# cheetah_driver_3.net
KiCad netlist of a schematic drawn in EAGLE
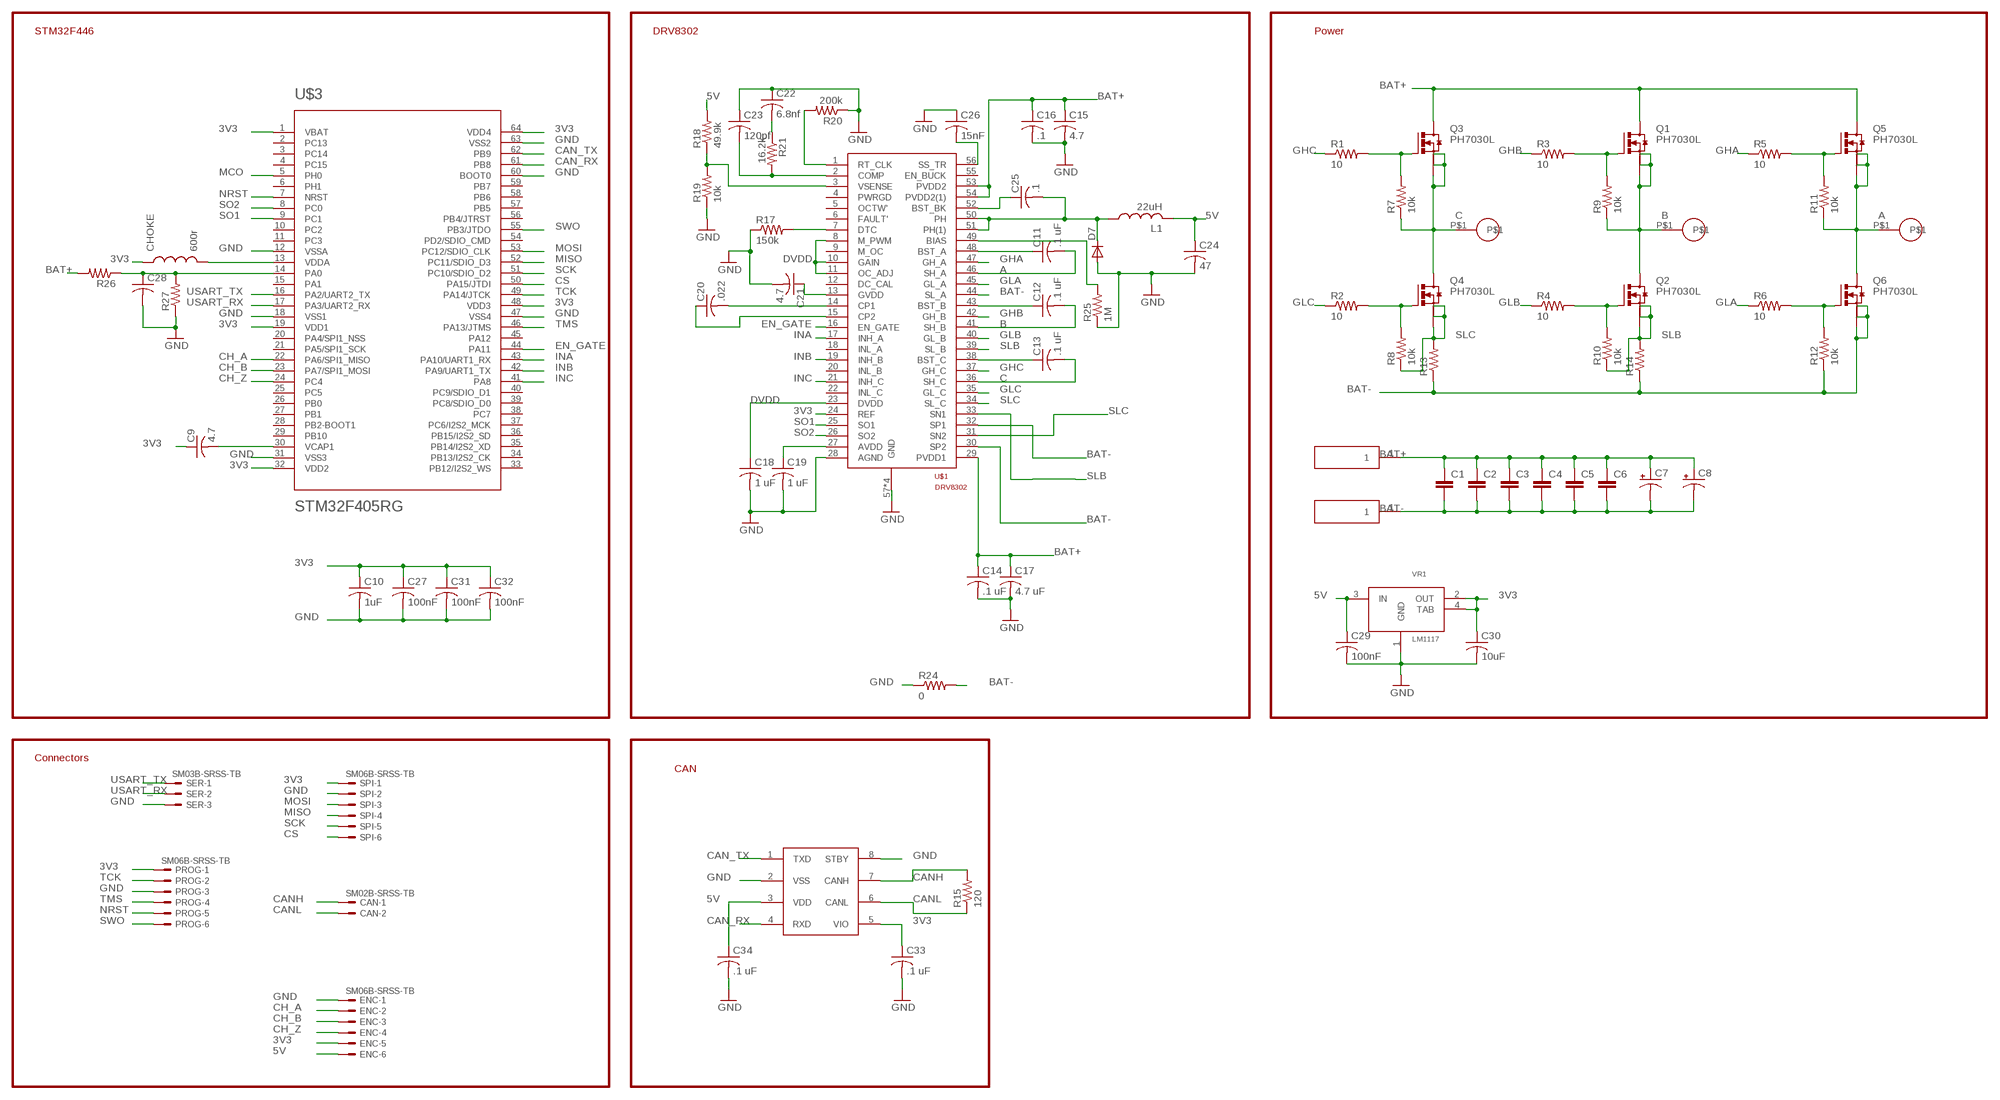
[diagram p0: schematic, sheet 1]

(export (version "E")
  (design (tool "Eeschema 10.0.6"))
  (components
    (comp (ref "C1")
      (value "C-EUC0805")
      (footprint "eagle-import:C0805")
      (libsource (lib "eagle-import") (part "C-EUC0805"))
    )
    (comp (ref "C2")
      (value "C-EUC0805")
      (footprint "eagle-import:C0805")
      (libsource (lib "eagle-import") (part "C-EUC0805"))
    )
    (comp (ref "C3")
      (value "C-EUC0805")
      (footprint "eagle-import:C0805")
      (libsource (lib "eagle-import") (part "C-EUC0805"))
    )
    (comp (ref "C4")
      (value "C-EUC0805")
      (footprint "eagle-import:C0805")
      (libsource (lib "eagle-import") (part "C-EUC0805"))
    )
    (comp (ref "C5")
      (value "C-EUC0805")
      (footprint "eagle-import:C0805")
      (libsource (lib "eagle-import") (part "C-EUC0805"))
    )
    (comp (ref "C6")
      (value "C-EUC0805")
      (footprint "eagle-import:C0805")
      (libsource (lib "eagle-import") (part "C-EUC0805"))
    )
    (comp (ref "C7")
      (value "CPOL-USE3.5-8")
      (footprint "eagle-import:E3,5-8")
      (libsource (lib "eagle-import") (part "CPOL-USE3.5-8"))
    )
    (comp (ref "C8")
      (value "CPOL-USE3.5-8")
      (footprint "eagle-import:E3,5-8")
      (libsource (lib "eagle-import") (part "CPOL-USE3.5-8"))
    )
    (comp (ref "C9")
      (value "4.7")
      (footprint "eagle-import:C0603")
      (libsource (lib "eagle-import") (part "C-USC0603"))
    )
    (comp (ref "C10")
      (value "1uF")
      (footprint "eagle-import:C0603")
      (libsource (lib "eagle-import") (part "C-USC0603"))
    )
    (comp (ref "C11")
      (value ".1 uF")
      (footprint "eagle-import:C0603")
      (libsource (lib "eagle-import") (part "C-USC0603"))
    )
    (comp (ref "C12")
      (value ".1 uF")
      (footprint "eagle-import:C0603")
      (libsource (lib "eagle-import") (part "C-USC0603"))
    )
    (comp (ref "C13")
      (value ".1 uF")
      (footprint "eagle-import:C0603")
      (libsource (lib "eagle-import") (part "C-USC0603"))
    )
    (comp (ref "C14")
      (value ".1 uF")
      (footprint "eagle-import:C0603")
      (libsource (lib "eagle-import") (part "C-USC0603"))
    )
    (comp (ref "C15")
      (value "4.7")
      (footprint "eagle-import:C0805")
      (libsource (lib "eagle-import") (part "C-USC0805"))
    )
    (comp (ref "C16")
      (value ".1")
      (footprint "eagle-import:C0603")
      (libsource (lib "eagle-import") (part "C-USC0603"))
    )
    (comp (ref "C17")
      (value "4.7 uF")
      (footprint "eagle-import:C0805")
      (libsource (lib "eagle-import") (part "C-USC0805"))
    )
    (comp (ref "C18")
      (value "1 uF")
      (footprint "eagle-import:C0603")
      (libsource (lib "eagle-import") (part "C-USC0603"))
    )
    (comp (ref "C19")
      (value "1 uF")
      (footprint "eagle-import:C0603")
      (libsource (lib "eagle-import") (part "C-USC0603"))
    )
    (comp (ref "C20")
      (value ".022")
      (footprint "eagle-import:C0603")
      (libsource (lib "eagle-import") (part "C-USC0603"))
    )
    (comp (ref "C21")
      (value "4.7")
      (footprint "eagle-import:C0805")
      (libsource (lib "eagle-import") (part "C-USC0805"))
    )
    (comp (ref "C22")
      (value "6.8nf")
      (footprint "eagle-import:C0603")
      (libsource (lib "eagle-import") (part "C-USC0603"))
    )
    (comp (ref "C23")
      (value "120pf")
      (footprint "eagle-import:C0603")
      (libsource (lib "eagle-import") (part "C-USC0603"))
    )
    (comp (ref "C24")
      (value "47")
      (footprint "eagle-import:C1210")
      (libsource (lib "eagle-import") (part "C-USC1210"))
    )
    (comp (ref "C25")
      (value ".1")
      (footprint "eagle-import:C0603")
      (libsource (lib "eagle-import") (part "C-USC0603"))
    )
    (comp (ref "C26")
      (value "15nF")
      (footprint "eagle-import:C0603")
      (libsource (lib "eagle-import") (part "C-USC0603"))
    )
    (comp (ref "C27")
      (value "100nF")
      (footprint "eagle-import:C0603")
      (libsource (lib "eagle-import") (part "C-USC0603"))
    )
    (comp (ref "C28")
      (value "C-USC0603")
      (footprint "eagle-import:C0603")
      (libsource (lib "eagle-import") (part "C-USC0603"))
    )
    (comp (ref "C29")
      (value "100nF")
      (footprint "eagle-import:C0603")
      (libsource (lib "eagle-import") (part "C-USC0603"))
    )
    (comp (ref "C30")
      (value "10uF")
      (footprint "eagle-import:C0603")
      (libsource (lib "eagle-import") (part "C-USC0603"))
    )
    (comp (ref "C31")
      (value "100nF")
      (footprint "eagle-import:C0603")
      (libsource (lib "eagle-import") (part "C-USC0603"))
    )
    (comp (ref "C32")
      (value "100nF")
      (footprint "eagle-import:C0603")
      (libsource (lib "eagle-import") (part "C-USC0603"))
    )
    (comp (ref "C33")
      (value ".1 uF")
      (footprint "eagle-import:C0603K")
      (libsource (lib "eagle-import") (part "C-USC0603K"))
    )
    (comp (ref "C34")
      (value ".1 uF")
      (footprint "eagle-import:C0603K")
      (libsource (lib "eagle-import") (part "C-USC0603K"))
    )
    (comp (ref "CAN")
      (value "SM02B-SRSS-TB")
      (footprint "eagle-import:SM02B-SRSS-TB")
      (libsource (lib "eagle-import") (part "?M02B-SRSS-TBS"))
    )
    (comp (ref "CHOKE")
      (value "600r")
      (footprint "eagle-import:0603")
      (libsource (lib "eagle-import") (part "INDUCTOR0603"))
    )
    (comp (ref "D7")
      (value "DIODE-DO-214AC")
      (footprint "eagle-import:DO-214AC")
      (libsource (lib "eagle-import") (part "DIODE-DO-214AC"))
    )
    (comp (ref "ENC")
      (value "SM06B-SRSS-TB")
      (footprint "eagle-import:SM06B-SRSS-TB")
      (libsource (lib "eagle-import") (part "?M06B-SRSS-TBS"))
    )
    (comp (ref "J4")
      (value "0.125_PAD")
      (footprint "eagle-import:0.125_PAD")
      (libsource (lib "eagle-import") (part "0.125_PAD"))
    )
    (comp (ref "J5")
      (value "0.125_PAD")
      (footprint "eagle-import:0.125_PAD")
      (libsource (lib "eagle-import") (part "0.125_PAD"))
    )
    (comp (ref "L1")
      (value "22uH")
      (footprint "eagle-import:L4532P")
      (libsource (lib "eagle-import") (part "L-USL4532P"))
    )
    (comp (ref "PROG")
      (value "SM06B-SRSS-TB")
      (footprint "eagle-import:SM06B-SRSS-TB")
      (libsource (lib "eagle-import") (part "?M06B-SRSS-TBS"))
    )
    (comp (ref "Q1")
      (value "PH7030L")
      (footprint "eagle-import:SOT669")
      (libsource (lib "eagle-import") (part "PH7030L"))
    )
    (comp (ref "Q2")
      (value "PH7030L")
      (footprint "eagle-import:SOT669")
      (libsource (lib "eagle-import") (part "PH7030L"))
    )
    (comp (ref "Q3")
      (value "PH7030L")
      (footprint "eagle-import:SOT669")
      (libsource (lib "eagle-import") (part "PH7030L"))
    )
    (comp (ref "Q4")
      (value "PH7030L")
      (footprint "eagle-import:SOT669")
      (libsource (lib "eagle-import") (part "PH7030L"))
    )
    (comp (ref "Q5")
      (value "PH7030L")
      (footprint "eagle-import:SOT669")
      (libsource (lib "eagle-import") (part "PH7030L"))
    )
    (comp (ref "Q6")
      (value "PH7030L")
      (footprint "eagle-import:SOT669")
      (libsource (lib "eagle-import") (part "PH7030L"))
    )
    (comp (ref "R1")
      (value "10")
      (footprint "eagle-import:R0603")
      (libsource (lib "eagle-import") (part "R-US_R0603"))
    )
    (comp (ref "R2")
      (value "10")
      (footprint "eagle-import:R0603")
      (libsource (lib "eagle-import") (part "R-US_R0603"))
    )
    (comp (ref "R3")
      (value "10")
      (footprint "eagle-import:R0603")
      (libsource (lib "eagle-import") (part "R-US_R0603"))
    )
    (comp (ref "R4")
      (value "10")
      (footprint "eagle-import:R0603")
      (libsource (lib "eagle-import") (part "R-US_R0603"))
    )
    (comp (ref "R5")
      (value "10")
      (footprint "eagle-import:R0603")
      (libsource (lib "eagle-import") (part "R-US_R0603"))
    )
    (comp (ref "R6")
      (value "10")
      (footprint "eagle-import:R0603")
      (libsource (lib "eagle-import") (part "R-US_R0603"))
    )
    (comp (ref "R7")
      (value "10k")
      (footprint "eagle-import:R0603")
      (libsource (lib "eagle-import") (part "R-US_R0603"))
    )
    (comp (ref "R8")
      (value "10k")
      (footprint "eagle-import:R0603")
      (libsource (lib "eagle-import") (part "R-US_R0603"))
    )
    (comp (ref "R9")
      (value "10k")
      (footprint "eagle-import:R0603")
      (libsource (lib "eagle-import") (part "R-US_R0603"))
    )
    (comp (ref "R10")
      (value "10k")
      (footprint "eagle-import:R0603")
      (libsource (lib "eagle-import") (part "R-US_R0603"))
    )
    (comp (ref "R11")
      (value "10k")
      (footprint "eagle-import:R0603")
      (libsource (lib "eagle-import") (part "R-US_R0603"))
    )
    (comp (ref "R12")
      (value "10k")
      (footprint "eagle-import:R0603")
      (libsource (lib "eagle-import") (part "R-US_R0603"))
    )
    (comp (ref "R13")
      (value "R-US_R1210")
      (footprint "eagle-import:R1210")
      (libsource (lib "eagle-import") (part "R-US_R1210"))
    )
    (comp (ref "R14")
      (value "R-US_R1210")
      (footprint "eagle-import:R1210")
      (libsource (lib "eagle-import") (part "R-US_R1210"))
    )
    (comp (ref "R15")
      (value "120")
      (footprint "eagle-import:R0603")
      (libsource (lib "eagle-import") (part "R-US_R0603"))
    )
    (comp (ref "R17")
      (value "150k")
      (footprint "eagle-import:R0603")
      (libsource (lib "eagle-import") (part "R-US_R0603"))
    )
    (comp (ref "R18")
      (value "49.9k")
      (footprint "eagle-import:R0603")
      (libsource (lib "eagle-import") (part "R-US_R0603"))
    )
    (comp (ref "R19")
      (value "10k")
      (footprint "eagle-import:R0603")
      (libsource (lib "eagle-import") (part "R-US_R0603"))
    )
    (comp (ref "R20")
      (value "200k")
      (footprint "eagle-import:R0603")
      (libsource (lib "eagle-import") (part "R-US_R0603"))
    )
    (comp (ref "R21")
      (value "16.2k")
      (footprint "eagle-import:R0603")
      (libsource (lib "eagle-import") (part "R-US_R0603"))
    )
    (comp (ref "R24")
      (value "0")
      (footprint "eagle-import:R0603")
      (libsource (lib "eagle-import") (part "R-US_R0603"))
    )
    (comp (ref "R25")
      (value "1M")
      (footprint "eagle-import:R0603")
      (libsource (lib "eagle-import") (part "R-US_R0603"))
    )
    (comp (ref "R26")
      (value "R-US_R0603")
      (footprint "eagle-import:R0603")
      (libsource (lib "eagle-import") (part "R-US_R0603"))
    )
    (comp (ref "R27")
      (value "R-US_R0603")
      (footprint "eagle-import:R0603")
      (libsource (lib "eagle-import") (part "R-US_R0603"))
    )
    (comp (ref "SER")
      (value "SM03B-SRSS-TB")
      (footprint "eagle-import:SM03B-SRSS-TB")
      (libsource (lib "eagle-import") (part "?M03B-SRSS-TBS"))
    )
    (comp (ref "SPI")
      (value "SM06B-SRSS-TB")
      (footprint "eagle-import:SM06B-SRSS-TB")
      (libsource (lib "eagle-import") (part "?M06B-SRSS-TBS"))
    )
    (comp (ref "U$1")
      (value "DRV8302")
      (footprint "eagle-import:HTSSOP56")
      (libsource (lib "eagle-import") (part "DRV8302"))
    )
    (comp (ref "U$2")
      (value "18_AWG_PAD")
      (footprint "eagle-import:18_AWG_PAD")
      (libsource (lib "eagle-import") (part "18_AWG_PAD"))
    )
    (comp (ref "U$3")
      (value "STM32F405RG")
      (footprint "eagle-import:TQFP64")
      (libsource (lib "eagle-import") (part "STM32F405RG"))
    )
    (comp (ref "U$4")
      (value "18_AWG_PAD")
      (footprint "eagle-import:18_AWG_PAD")
      (libsource (lib "eagle-import") (part "18_AWG_PAD"))
    )
    (comp (ref "U$5")
      (value "18_AWG_PAD")
      (footprint "eagle-import:18_AWG_PAD")
      (libsource (lib "eagle-import") (part "18_AWG_PAD"))
    )
    (comp (ref "U$6")
      (value "MCP2561")
      (footprint "eagle-import:SO08")
      (libsource (lib "eagle-import") (part "MCP2561"))
    )
    (comp (ref "VR1")
      (value "LM1117")
      (footprint "eagle-import:SOT-223")
      (libsource (lib "eagle-import") (part "LM1117"))
    )
  )
  (nets
    (net (code "1") (name "/3V3") (class "Default")
      (node (ref "C10") (pin "1") (pinfunction "1_1") (pintype "passive"))
      (node (ref "C27") (pin "1") (pinfunction "1_1") (pintype "passive"))
      (node (ref "C30") (pin "1") (pinfunction "1_1") (pintype "passive"))
      (node (ref "C31") (pin "1") (pinfunction "1_1") (pintype "passive"))
      (node (ref "C32") (pin "1") (pinfunction "1_1") (pintype "passive"))
      (node (ref "C33") (pin "1") (pinfunction "1_1") (pintype "passive"))
      (node (ref "C9") (pin "1") (pinfunction "1_1") (pintype "passive"))
      (node (ref "CHOKE") (pin "1") (pinfunction "1_1") (pintype "passive"))
      (node (ref "ENC") (pin "5") (pinfunction "S_5") (pintype "passive"))
      (node (ref "PROG") (pin "1") (pinfunction "S_1") (pintype "passive"))
      (node (ref "SPI") (pin "1") (pinfunction "S_1") (pintype "passive"))
      (node (ref "U$1") (pin "24") (pinfunction "REF_24") (pintype "bidirectional"))
      (node (ref "U$3") (pin "1") (pinfunction "VBAT_1") (pintype "bidirectional"))
      (node (ref "U$3") (pin "19") (pinfunction "VDD1_19") (pintype "bidirectional"))
      (node (ref "U$3") (pin "32") (pinfunction "VDD2_32") (pintype "bidirectional"))
      (node (ref "U$3") (pin "48") (pinfunction "VDD3_48") (pintype "bidirectional"))
      (node (ref "U$3") (pin "64") (pinfunction "VDD4_64") (pintype "bidirectional"))
      (node (ref "U$6") (pin "5") (pinfunction "VIO_5") (pintype "bidirectional"))
      (node (ref "VR1") (pin "2") (pinfunction "OUT_2") (pintype "bidirectional"))
      (node (ref "VR1") (pin "4") (pinfunction "TAB_4") (pintype "bidirectional"))
    )
    (net (code "2") (name "/5V") (class "Default")
      (node (ref "C24") (pin "1") (pinfunction "1_1") (pintype "passive"))
      (node (ref "C29") (pin "1") (pinfunction "1_1") (pintype "passive"))
      (node (ref "C34") (pin "1") (pinfunction "1_1") (pintype "passive"))
      (node (ref "ENC") (pin "6") (pinfunction "S_6") (pintype "passive"))
      (node (ref "L1") (pin "2") (pinfunction "2_2") (pintype "passive"))
      (node (ref "R18") (pin "2") (pinfunction "2_2") (pintype "passive"))
      (node (ref "U$6") (pin "3") (pinfunction "VDD_3") (pintype "bidirectional"))
      (node (ref "VR1") (pin "3") (pinfunction "IN_3") (pintype "bidirectional"))
    )
    (net (code "3") (name "/A") (class "Default")
      (node (ref "C11") (pin "2") (pinfunction "2_2") (pintype "passive"))
      (node (ref "Q5") (pin "1") (pinfunction "S_1") (pintype "passive"))
      (node (ref "Q5") (pin "2") (pinfunction "S_2") (pintype "passive"))
      (node (ref "Q5") (pin "3") (pinfunction "S_3") (pintype "passive"))
      (node (ref "Q6") (pin "MB") (pinfunction "D_MB") (pintype "passive"))
      (node (ref "R11") (pin "1") (pinfunction "1_1") (pintype "passive"))
      (node (ref "U$1") (pin "46") (pinfunction "SH_A_46") (pintype "bidirectional"))
      (node (ref "U$5") (pin "P$1") (pinfunction "P$1_P$1") (pintype "bidirectional"))
    )
    (net (code "4") (name "/B") (class "Default")
      (node (ref "C12") (pin "2") (pinfunction "2_2") (pintype "passive"))
      (node (ref "Q1") (pin "1") (pinfunction "S_1") (pintype "passive"))
      (node (ref "Q1") (pin "2") (pinfunction "S_2") (pintype "passive"))
      (node (ref "Q1") (pin "3") (pinfunction "S_3") (pintype "passive"))
      (node (ref "Q2") (pin "MB") (pinfunction "D_MB") (pintype "passive"))
      (node (ref "R9") (pin "1") (pinfunction "1_1") (pintype "passive"))
      (node (ref "U$1") (pin "41") (pinfunction "SH_B_41") (pintype "bidirectional"))
      (node (ref "U$4") (pin "P$1") (pinfunction "P$1_P$1") (pintype "bidirectional"))
    )
    (net (code "5") (name "/BAT+") (class "Default")
      (node (ref "C1") (pin "1") (pinfunction "1_1") (pintype "passive"))
      (node (ref "C14") (pin "1") (pinfunction "1_1") (pintype "passive"))
      (node (ref "C15") (pin "1") (pinfunction "1_1") (pintype "passive"))
      (node (ref "C16") (pin "1") (pinfunction "1_1") (pintype "passive"))
      (node (ref "C17") (pin "1") (pinfunction "1_1") (pintype "passive"))
      (node (ref "C2") (pin "1") (pinfunction "1_1") (pintype "passive"))
      (node (ref "C3") (pin "1") (pinfunction "1_1") (pintype "passive"))
      (node (ref "C4") (pin "1") (pinfunction "1_1") (pintype "passive"))
      (node (ref "C5") (pin "1") (pinfunction "1_1") (pintype "passive"))
      (node (ref "C6") (pin "1") (pinfunction "1_1") (pintype "passive"))
      (node (ref "C7") (pin "+") (pinfunction "+_+") (pintype "passive"))
      (node (ref "C8") (pin "+") (pinfunction "+_+") (pintype "passive"))
      (node (ref "J4") (pin "1") (pinfunction "1_1") (pintype "bidirectional"))
      (node (ref "Q1") (pin "MB") (pinfunction "D_MB") (pintype "passive"))
      (node (ref "Q3") (pin "MB") (pinfunction "D_MB") (pintype "passive"))
      (node (ref "Q5") (pin "MB") (pinfunction "D_MB") (pintype "passive"))
      (node (ref "R26") (pin "2") (pinfunction "2_2") (pintype "passive"))
      (node (ref "U$1") (pin "29") (pinfunction "PVDD1_29") (pintype "bidirectional"))
      (node (ref "U$1") (pin "53") (pinfunction "PVDD2_53") (pintype "bidirectional"))
      (node (ref "U$1") (pin "54") (pinfunction "PVDD2(1)_54") (pintype "bidirectional"))
    )
    (net (code "6") (name "/BAT-") (class "Default")
      (node (ref "C1") (pin "2") (pinfunction "2_2") (pintype "passive"))
      (node (ref "C2") (pin "2") (pinfunction "2_2") (pintype "passive"))
      (node (ref "C3") (pin "2") (pinfunction "2_2") (pintype "passive"))
      (node (ref "C4") (pin "2") (pinfunction "2_2") (pintype "passive"))
      (node (ref "C5") (pin "2") (pinfunction "2_2") (pintype "passive"))
      (node (ref "C6") (pin "2") (pinfunction "2_2") (pintype "passive"))
      (node (ref "C7") (pin "-") (pinfunction "-_-") (pintype "passive"))
      (node (ref "C8") (pin "-") (pinfunction "-_-") (pintype "passive"))
      (node (ref "J5") (pin "1") (pinfunction "1_1") (pintype "bidirectional"))
      (node (ref "Q6") (pin "1") (pinfunction "S_1") (pintype "passive"))
      (node (ref "Q6") (pin "2") (pinfunction "S_2") (pintype "passive"))
      (node (ref "Q6") (pin "3") (pinfunction "S_3") (pintype "passive"))
      (node (ref "R12") (pin "1") (pinfunction "1_1") (pintype "passive"))
      (node (ref "R13") (pin "1") (pinfunction "1_1") (pintype "passive"))
      (node (ref "R14") (pin "1") (pinfunction "1_1") (pintype "passive"))
      (node (ref "R24") (pin "2") (pinfunction "2_2") (pintype "passive"))
      (node (ref "U$1") (pin "30") (pinfunction "SP2_30") (pintype "bidirectional"))
      (node (ref "U$1") (pin "32") (pinfunction "SP1_32") (pintype "bidirectional"))
      (node (ref "U$1") (pin "44") (pinfunction "SL_A_44") (pintype "bidirectional"))
    )
    (net (code "7") (name "/C") (class "Default")
      (node (ref "C13") (pin "2") (pinfunction "2_2") (pintype "passive"))
      (node (ref "Q3") (pin "1") (pinfunction "S_1") (pintype "passive"))
      (node (ref "Q3") (pin "2") (pinfunction "S_2") (pintype "passive"))
      (node (ref "Q3") (pin "3") (pinfunction "S_3") (pintype "passive"))
      (node (ref "Q4") (pin "MB") (pinfunction "D_MB") (pintype "passive"))
      (node (ref "R7") (pin "1") (pinfunction "1_1") (pintype "passive"))
      (node (ref "U$1") (pin "36") (pinfunction "SH_C_36") (pintype "bidirectional"))
      (node (ref "U$2") (pin "P$1") (pinfunction "P$1_P$1") (pintype "bidirectional"))
    )
    (net (code "8") (name "/CANH") (class "Default")
      (node (ref "CAN") (pin "1") (pinfunction "S_1") (pintype "passive"))
      (node (ref "R15") (pin "2") (pinfunction "2_2") (pintype "passive"))
      (node (ref "U$6") (pin "7") (pinfunction "CANH_7") (pintype "bidirectional"))
    )
    (net (code "9") (name "/CANL") (class "Default")
      (node (ref "CAN") (pin "2") (pinfunction "S_2") (pintype "passive"))
      (node (ref "R15") (pin "1") (pinfunction "1_1") (pintype "passive"))
      (node (ref "U$6") (pin "6") (pinfunction "CANL_6") (pintype "bidirectional"))
    )
    (net (code "10") (name "/CAN_RX") (class "Default")
      (node (ref "U$3") (pin "61") (pinfunction "PB8_61") (pintype "bidirectional"))
      (node (ref "U$6") (pin "4") (pinfunction "RXD_4") (pintype "bidirectional"))
    )
    (net (code "11") (name "/CAN_TX") (class "Default")
      (node (ref "U$3") (pin "62") (pinfunction "PB9_62") (pintype "bidirectional"))
      (node (ref "U$6") (pin "1") (pinfunction "TXD_1") (pintype "bidirectional"))
    )
    (net (code "12") (name "/CH_A") (class "Default")
      (node (ref "ENC") (pin "2") (pinfunction "S_2") (pintype "passive"))
      (node (ref "U$3") (pin "22") (pinfunction "PA6/SPI1_MISO_22") (pintype "bidirectional"))
    )
    (net (code "13") (name "/CH_B") (class "Default")
      (node (ref "ENC") (pin "3") (pinfunction "S_3") (pintype "passive"))
      (node (ref "U$3") (pin "23") (pinfunction "PA7/SPI1_MOSI_23") (pintype "bidirectional"))
    )
    (net (code "14") (name "/CH_Z") (class "Default")
      (node (ref "ENC") (pin "4") (pinfunction "S_4") (pintype "passive"))
      (node (ref "U$3") (pin "24") (pinfunction "PC4_24") (pintype "bidirectional"))
    )
    (net (code "15") (name "/CS") (class "Default")
      (node (ref "SPI") (pin "6") (pinfunction "S_6") (pintype "passive"))
      (node (ref "U$3") (pin "50") (pinfunction "PA15/JTDI_50") (pintype "bidirectional"))
    )
    (net (code "16") (name "/DVDD") (class "Default")
      (node (ref "C18") (pin "1") (pinfunction "1_1") (pintype "passive"))
      (node (ref "U$1") (pin "10") (pinfunction "GAIN_10") (pintype "bidirectional"))
      (node (ref "U$1") (pin "11") (pinfunction "OC_ADJ_11") (pintype "bidirectional"))
      (node (ref "U$1") (pin "23") (pinfunction "DVDD_23") (pintype "bidirectional"))
      (node (ref "U$1") (pin "8") (pinfunction "M_PWM_8") (pintype "bidirectional"))
    )
    (net (code "17") (name "/EN_GATE") (class "Default")
      (node (ref "U$1") (pin "16") (pinfunction "EN_GATE_16") (pintype "bidirectional"))
      (node (ref "U$3") (pin "44") (pinfunction "PA11_44") (pintype "bidirectional"))
    )
    (net (code "18") (name "/GHA") (class "Default")
      (node (ref "R5") (pin "1") (pinfunction "1_1") (pintype "passive"))
      (node (ref "U$1") (pin "47") (pinfunction "GH_A_47") (pintype "bidirectional"))
    )
    (net (code "19") (name "/GHB") (class "Default")
      (node (ref "R3") (pin "1") (pinfunction "1_1") (pintype "passive"))
      (node (ref "U$1") (pin "42") (pinfunction "GH_B_42") (pintype "bidirectional"))
    )
    (net (code "20") (name "/GHC") (class "Default")
      (node (ref "R1") (pin "1") (pinfunction "1_1") (pintype "passive"))
      (node (ref "U$1") (pin "37") (pinfunction "GH_C_37") (pintype "bidirectional"))
    )
    (net (code "21") (name "/GLA") (class "Default")
      (node (ref "R6") (pin "1") (pinfunction "1_1") (pintype "passive"))
      (node (ref "U$1") (pin "45") (pinfunction "GL_A_45") (pintype "bidirectional"))
    )
    (net (code "22") (name "/GLB") (class "Default")
      (node (ref "R4") (pin "1") (pinfunction "1_1") (pintype "passive"))
      (node (ref "U$1") (pin "40") (pinfunction "GL_B_40") (pintype "bidirectional"))
    )
    (net (code "23") (name "/GLC") (class "Default")
      (node (ref "R2") (pin "1") (pinfunction "1_1") (pintype "passive"))
      (node (ref "U$1") (pin "35") (pinfunction "GL_C_35") (pintype "bidirectional"))
    )
    (net (code "24") (name "/INA") (class "Default")
      (node (ref "U$1") (pin "17") (pinfunction "INH_A_17") (pintype "bidirectional"))
      (node (ref "U$3") (pin "43") (pinfunction "PA10/UART1_RX_43") (pintype "bidirectional"))
    )
    (net (code "25") (name "/INB") (class "Default")
      (node (ref "U$1") (pin "19") (pinfunction "INH_B_19") (pintype "bidirectional"))
      (node (ref "U$3") (pin "42") (pinfunction "PA9/UART1_TX_42") (pintype "bidirectional"))
    )
    (net (code "26") (name "/INC") (class "Default")
      (node (ref "U$1") (pin "21") (pinfunction "INH_C_21") (pintype "bidirectional"))
      (node (ref "U$3") (pin "41") (pinfunction "PA8_41") (pintype "bidirectional"))
    )
    (net (code "27") (name "/MCO") (class "Default")
      (node (ref "U$3") (pin "5") (pinfunction "PH0_5") (pintype "bidirectional"))
    )
    (net (code "28") (name "/MISO") (class "Default")
      (node (ref "SPI") (pin "4") (pinfunction "S_4") (pintype "passive"))
      (node (ref "U$3") (pin "52") (pinfunction "PC11/SDIO_D3_52") (pintype "bidirectional"))
    )
    (net (code "29") (name "/MOSI") (class "Default")
      (node (ref "SPI") (pin "3") (pinfunction "S_3") (pintype "passive"))
      (node (ref "U$3") (pin "53") (pinfunction "PC12/SDIO_CLK_53") (pintype "bidirectional"))
    )
    (net (code "30") (name "/NRST") (class "Default")
      (node (ref "PROG") (pin "5") (pinfunction "S_5") (pintype "passive"))
      (node (ref "U$3") (pin "7") (pinfunction "NRST_7") (pintype "bidirectional"))
    )
    (net (code "31") (name "/SCK") (class "Default")
      (node (ref "SPI") (pin "5") (pinfunction "S_5") (pintype "passive"))
      (node (ref "U$3") (pin "51") (pinfunction "PC10/SDIO_D2_51") (pintype "bidirectional"))
    )
    (net (code "32") (name "/SLB") (class "Default")
      (node (ref "Q2") (pin "1") (pinfunction "S_1") (pintype "passive"))
      (node (ref "Q2") (pin "2") (pinfunction "S_2") (pintype "passive"))
      (node (ref "Q2") (pin "3") (pinfunction "S_3") (pintype "passive"))
      (node (ref "R10") (pin "1") (pinfunction "1_1") (pintype "passive"))
      (node (ref "R14") (pin "2") (pinfunction "2_2") (pintype "passive"))
      (node (ref "U$1") (pin "33") (pinfunction "SN1_33") (pintype "bidirectional"))
      (node (ref "U$1") (pin "39") (pinfunction "SL_B_39") (pintype "bidirectional"))
    )
    (net (code "33") (name "/SLC") (class "Default")
      (node (ref "Q4") (pin "1") (pinfunction "S_1") (pintype "passive"))
      (node (ref "Q4") (pin "2") (pinfunction "S_2") (pintype "passive"))
      (node (ref "Q4") (pin "3") (pinfunction "S_3") (pintype "passive"))
      (node (ref "R13") (pin "2") (pinfunction "2_2") (pintype "passive"))
      (node (ref "R8") (pin "1") (pinfunction "1_1") (pintype "passive"))
      (node (ref "U$1") (pin "31") (pinfunction "SN2_31") (pintype "bidirectional"))
      (node (ref "U$1") (pin "34") (pinfunction "SL_C_34") (pintype "bidirectional"))
    )
    (net (code "34") (name "/SO1") (class "Default")
      (node (ref "U$1") (pin "25") (pinfunction "SO1_25") (pintype "bidirectional"))
      (node (ref "U$3") (pin "9") (pinfunction "PC1_9") (pintype "bidirectional"))
    )
    (net (code "35") (name "/SO2") (class "Default")
      (node (ref "U$1") (pin "26") (pinfunction "SO2_26") (pintype "bidirectional"))
      (node (ref "U$3") (pin "8") (pinfunction "PC0_8") (pintype "bidirectional"))
    )
    (net (code "36") (name "/SWO") (class "Default")
      (node (ref "PROG") (pin "6") (pinfunction "S_6") (pintype "passive"))
      (node (ref "U$3") (pin "55") (pinfunction "PB3/JTDO_55") (pintype "bidirectional"))
    )
    (net (code "37") (name "/TCK") (class "Default")
      (node (ref "PROG") (pin "2") (pinfunction "S_2") (pintype "passive"))
      (node (ref "U$3") (pin "49") (pinfunction "PA14/JTCK_49") (pintype "bidirectional"))
    )
    (net (code "38") (name "/TMS") (class "Default")
      (node (ref "PROG") (pin "4") (pinfunction "S_4") (pintype "passive"))
      (node (ref "U$3") (pin "46") (pinfunction "PA13/JTMS_46") (pintype "bidirectional"))
    )
    (net (code "39") (name "/USART_RX") (class "Default")
      (node (ref "SER") (pin "2") (pinfunction "S_2") (pintype "passive"))
      (node (ref "U$3") (pin "17") (pinfunction "PA3/UART2_RX_17") (pintype "bidirectional"))
    )
    (net (code "40") (name "/USART_TX") (class "Default")
      (node (ref "SER") (pin "1") (pinfunction "S_1") (pintype "passive"))
      (node (ref "U$3") (pin "16") (pinfunction "PA2/UART2_TX_16") (pintype "bidirectional"))
    )
    (net (code "41") (name "GND") (class "Default")
      (node (ref "C10") (pin "2") (pinfunction "2_2") (pintype "passive"))
      (node (ref "C14") (pin "2") (pinfunction "2_2") (pintype "passive"))
      (node (ref "C15") (pin "2") (pinfunction "2_2") (pintype "passive"))
      (node (ref "C16") (pin "2") (pinfunction "2_2") (pintype "passive"))
      (node (ref "C17") (pin "2") (pinfunction "2_2") (pintype "passive"))
      (node (ref "C18") (pin "2") (pinfunction "2_2") (pintype "passive"))
      (node (ref "C19") (pin "2") (pinfunction "2_2") (pintype "passive"))
      (node (ref "C21") (pin "2") (pinfunction "2_2") (pintype "passive"))
      (node (ref "C22") (pin "1") (pinfunction "1_1") (pintype "passive"))
      (node (ref "C23") (pin "1") (pinfunction "1_1") (pintype "passive"))
      (node (ref "C24") (pin "2") (pinfunction "2_2") (pintype "passive"))
      (node (ref "C26") (pin "1") (pinfunction "1_1") (pintype "passive"))
      (node (ref "C27") (pin "2") (pinfunction "2_2") (pintype "passive"))
      (node (ref "C28") (pin "2") (pinfunction "2_2") (pintype "passive"))
      (node (ref "C29") (pin "2") (pinfunction "2_2") (pintype "passive"))
      (node (ref "C30") (pin "2") (pinfunction "2_2") (pintype "passive"))
      (node (ref "C31") (pin "2") (pinfunction "2_2") (pintype "passive"))
      (node (ref "C32") (pin "2") (pinfunction "2_2") (pintype "passive"))
      (node (ref "C33") (pin "2") (pinfunction "2_2") (pintype "passive"))
      (node (ref "C34") (pin "2") (pinfunction "2_2") (pintype "passive"))
      (node (ref "D7") (pin "A") (pinfunction "A_A") (pintype "passive"))
      (node (ref "ENC") (pin "1") (pinfunction "S_1") (pintype "passive"))
      (node (ref "PROG") (pin "3") (pinfunction "S_3") (pintype "passive"))
      (node (ref "R17") (pin "1") (pinfunction "1_1") (pintype "passive"))
      (node (ref "R19") (pin "1") (pinfunction "1_1") (pintype "passive"))
      (node (ref "R20") (pin "1") (pinfunction "1_1") (pintype "passive"))
      (node (ref "R24") (pin "1") (pinfunction "1_1") (pintype "passive"))
      (node (ref "R25") (pin "1") (pinfunction "1_1") (pintype "passive"))
      (node (ref "R27") (pin "1") (pinfunction "1_1") (pintype "passive"))
      (node (ref "SER") (pin "3") (pinfunction "S_3") (pintype "passive"))
      (node (ref "SPI") (pin "2") (pinfunction "S_2") (pintype "passive"))
      (node (ref "U$1") (pin "28") (pinfunction "AGND_28") (pintype "bidirectional"))
      (node (ref "U$1") (pin "57") (pinfunction "GND_57") (pintype "bidirectional"))
      (node (ref "U$1") (pin "P$1") (pinfunction "GND_P$1") (pintype "bidirectional"))
      (node (ref "U$1") (pin "P$2") (pinfunction "GND_P$2") (pintype "bidirectional"))
      (node (ref "U$1") (pin "P$3") (pinfunction "GND_P$3") (pintype "bidirectional"))
      (node (ref "U$3") (pin "12") (pinfunction "VSSA_12") (pintype "bidirectional"))
      (node (ref "U$3") (pin "18") (pinfunction "VSS1_18") (pintype "bidirectional"))
      (node (ref "U$3") (pin "31") (pinfunction "VSS3_31") (pintype "bidirectional"))
      (node (ref "U$3") (pin "47") (pinfunction "VSS4_47") (pintype "bidirectional"))
      (node (ref "U$3") (pin "60") (pinfunction "BOOT0_60") (pintype "bidirectional"))
      (node (ref "U$3") (pin "63") (pinfunction "VSS2_63") (pintype "bidirectional"))
      (node (ref "U$6") (pin "2") (pinfunction "VSS_2") (pintype "bidirectional"))
      (node (ref "U$6") (pin "8") (pinfunction "STBY_8") (pintype "bidirectional"))
      (node (ref "VR1") (pin "1") (pinfunction "GND_1") (pintype "bidirectional"))
    )
    (net (code "42") (name "Net-(C22-Pad2)") (class "Default")
      (node (ref "C22") (pin "2") (pinfunction "2_2") (pintype "passive"))
      (node (ref "R21") (pin "1") (pinfunction "1_1") (pintype "passive"))
    )
    (net (code "43") (name "Net-(Q1-G)") (class "Default")
      (node (ref "Q1") (pin "4") (pinfunction "G_4") (pintype "passive"))
      (node (ref "R3") (pin "2") (pinfunction "2_2") (pintype "passive"))
      (node (ref "R9") (pin "2") (pinfunction "2_2") (pintype "passive"))
    )
    (net (code "44") (name "Net-(Q2-G)") (class "Default")
      (node (ref "Q2") (pin "4") (pinfunction "G_4") (pintype "passive"))
      (node (ref "R10") (pin "2") (pinfunction "2_2") (pintype "passive"))
      (node (ref "R4") (pin "2") (pinfunction "2_2") (pintype "passive"))
    )
    (net (code "45") (name "Net-(Q3-G)") (class "Default")
      (node (ref "Q3") (pin "4") (pinfunction "G_4") (pintype "passive"))
      (node (ref "R1") (pin "2") (pinfunction "2_2") (pintype "passive"))
      (node (ref "R7") (pin "2") (pinfunction "2_2") (pintype "passive"))
    )
    (net (code "46") (name "Net-(Q4-G)") (class "Default")
      (node (ref "Q4") (pin "4") (pinfunction "G_4") (pintype "passive"))
      (node (ref "R2") (pin "2") (pinfunction "2_2") (pintype "passive"))
      (node (ref "R8") (pin "2") (pinfunction "2_2") (pintype "passive"))
    )
    (net (code "47") (name "Net-(Q5-G)") (class "Default")
      (node (ref "Q5") (pin "4") (pinfunction "G_4") (pintype "passive"))
      (node (ref "R11") (pin "2") (pinfunction "2_2") (pintype "passive"))
      (node (ref "R5") (pin "2") (pinfunction "2_2") (pintype "passive"))
    )
    (net (code "48") (name "Net-(Q6-G)") (class "Default")
      (node (ref "Q6") (pin "4") (pinfunction "G_4") (pintype "passive"))
      (node (ref "R12") (pin "2") (pinfunction "2_2") (pintype "passive"))
      (node (ref "R6") (pin "2") (pinfunction "2_2") (pintype "passive"))
    )
    (net (code "49") (name "Net-(U$1-AVDD)") (class "Default")
      (node (ref "C19") (pin "1") (pinfunction "1_1") (pintype "passive"))
      (node (ref "U$1") (pin "27") (pinfunction "AVDD_27") (pintype "bidirectional"))
    )
    (net (code "50") (name "Net-(U$1-BIAS)") (class "Default")
      (node (ref "R25") (pin "2") (pinfunction "2_2") (pintype "passive"))
      (node (ref "U$1") (pin "49") (pinfunction "BIAS_49") (pintype "bidirectional"))
    )
    (net (code "51") (name "Net-(U$1-BST_A)") (class "Default")
      (node (ref "C11") (pin "1") (pinfunction "1_1") (pintype "passive"))
      (node (ref "U$1") (pin "48") (pinfunction "BST_A_48") (pintype "bidirectional"))
    )
    (net (code "52") (name "Net-(U$1-BST_B)") (class "Default")
      (node (ref "C12") (pin "1") (pinfunction "1_1") (pintype "passive"))
      (node (ref "U$1") (pin "43") (pinfunction "BST_B_43") (pintype "bidirectional"))
    )
    (net (code "53") (name "Net-(U$1-BST_BK)") (class "Default")
      (node (ref "C25") (pin "1") (pinfunction "1_1") (pintype "passive"))
      (node (ref "U$1") (pin "52") (pinfunction "BST_BK_52") (pintype "bidirectional"))
    )
    (net (code "54") (name "Net-(U$1-BST_C)") (class "Default")
      (node (ref "C13") (pin "1") (pinfunction "1_1") (pintype "passive"))
      (node (ref "U$1") (pin "38") (pinfunction "BST_C_38") (pintype "bidirectional"))
    )
    (net (code "55") (name "Net-(U$1-COMP)") (class "Default")
      (node (ref "C23") (pin "2") (pinfunction "2_2") (pintype "passive"))
      (node (ref "R21") (pin "2") (pinfunction "2_2") (pintype "passive"))
      (node (ref "U$1") (pin "2") (pinfunction "COMP_2") (pintype "bidirectional"))
    )
    (net (code "56") (name "Net-(U$1-CP1)") (class "Default")
      (node (ref "C20") (pin "2") (pinfunction "2_2") (pintype "passive"))
      (node (ref "U$1") (pin "14") (pinfunction "CP1_14") (pintype "bidirectional"))
    )
    (net (code "57") (name "Net-(U$1-CP2)") (class "Default")
      (node (ref "C20") (pin "1") (pinfunction "1_1") (pintype "passive"))
      (node (ref "U$1") (pin "15") (pinfunction "CP2_15") (pintype "bidirectional"))
    )
    (net (code "58") (name "Net-(U$1-DTC)") (class "Default")
      (node (ref "R17") (pin "2") (pinfunction "2_2") (pintype "passive"))
      (node (ref "U$1") (pin "7") (pinfunction "DTC_7") (pintype "bidirectional"))
    )
    (net (code "59") (name "Net-(U$1-GVDD)") (class "Default")
      (node (ref "C21") (pin "1") (pinfunction "1_1") (pintype "passive"))
      (node (ref "U$1") (pin "13") (pinfunction "GVDD_13") (pintype "bidirectional"))
    )
    (net (code "60") (name "Net-(U$1-PH(1))") (class "Default")
      (node (ref "C25") (pin "2") (pinfunction "2_2") (pintype "passive"))
      (node (ref "D7") (pin "C") (pinfunction "C_C") (pintype "passive"))
      (node (ref "L1") (pin "1") (pinfunction "1_1") (pintype "passive"))
      (node (ref "U$1") (pin "50") (pinfunction "PH_50") (pintype "bidirectional"))
      (node (ref "U$1") (pin "51") (pinfunction "PH(1)_51") (pintype "bidirectional"))
    )
    (net (code "61") (name "Net-(U$1-RT_CLK)") (class "Default")
      (node (ref "R20") (pin "2") (pinfunction "2_2") (pintype "passive"))
      (node (ref "U$1") (pin "1") (pinfunction "RT_CLK_1") (pintype "bidirectional"))
    )
    (net (code "62") (name "Net-(U$1-SS_TR)") (class "Default")
      (node (ref "C26") (pin "2") (pinfunction "2_2") (pintype "passive"))
      (node (ref "U$1") (pin "56") (pinfunction "SS_TR_56") (pintype "bidirectional"))
    )
    (net (code "63") (name "Net-(U$1-VSENSE)") (class "Default")
      (node (ref "R18") (pin "1") (pinfunction "1_1") (pintype "passive"))
      (node (ref "R19") (pin "2") (pinfunction "2_2") (pintype "passive"))
      (node (ref "U$1") (pin "3") (pinfunction "VSENSE_3") (pintype "bidirectional"))
    )
    (net (code "64") (name "Net-(U$3-PA0)") (class "Default")
      (node (ref "C28") (pin "1") (pinfunction "1_1") (pintype "passive"))
      (node (ref "R26") (pin "1") (pinfunction "1_1") (pintype "passive"))
      (node (ref "R27") (pin "2") (pinfunction "2_2") (pintype "passive"))
      (node (ref "U$3") (pin "14") (pinfunction "PA0_14") (pintype "bidirectional"))
    )
    (net (code "65") (name "Net-(U$3-VCAP1)") (class "Default")
      (node (ref "C9") (pin "2") (pinfunction "2_2") (pintype "passive"))
      (node (ref "U$3") (pin "30") (pinfunction "VCAP1_30") (pintype "bidirectional"))
    )
    (net (code "66") (name "Net-(U$3-VDDA)") (class "Default")
      (node (ref "CHOKE") (pin "2") (pinfunction "2_2") (pintype "passive"))
      (node (ref "U$3") (pin "13") (pinfunction "VDDA_13") (pintype "bidirectional"))
    )
    (net (code "67") (name "unconnected-(U$1-DC_CAL-Pad12)") (class "Default")
      (node (ref "U$1") (pin "12") (pinfunction "DC_CAL_12") (pintype "bidirectional"))
    )
    (net (code "68") (name "unconnected-(U$1-EN_BUCK-Pad55)") (class "Default")
      (node (ref "U$1") (pin "55") (pinfunction "EN_BUCK_55") (pintype "bidirectional"))
    )
    (net (code "69") (name "unconnected-(U$1-FAULT'-Pad6)") (class "Default")
      (node (ref "U$1") (pin "6") (pinfunction "FAULT'_6") (pintype "bidirectional"))
    )
    (net (code "70") (name "unconnected-(U$1-INL_A-Pad18)") (class "Default")
      (node (ref "U$1") (pin "18") (pinfunction "INL_A_18") (pintype "bidirectional"))
    )
    (net (code "71") (name "unconnected-(U$1-INL_B-Pad20)") (class "Default")
      (node (ref "U$1") (pin "20") (pinfunction "INL_B_20") (pintype "bidirectional"))
    )
    (net (code "72") (name "unconnected-(U$1-INL_C-Pad22)") (class "Default")
      (node (ref "U$1") (pin "22") (pinfunction "INL_C_22") (pintype "bidirectional"))
    )
    (net (code "73") (name "unconnected-(U$1-M_OC-Pad9)") (class "Default")
      (node (ref "U$1") (pin "9") (pinfunction "M_OC_9") (pintype "bidirectional"))
    )
    (net (code "74") (name "unconnected-(U$1-OCTW'-Pad5)") (class "Default")
      (node (ref "U$1") (pin "5") (pinfunction "OCTW'_5") (pintype "bidirectional"))
    )
    (net (code "75") (name "unconnected-(U$1-PWRGD-Pad4)") (class "Default")
      (node (ref "U$1") (pin "4") (pinfunction "PWRGD_4") (pintype "bidirectional"))
    )
    (net (code "76") (name "unconnected-(U$3-PA1-Pad15)") (class "Default")
      (node (ref "U$3") (pin "15") (pinfunction "PA1_15") (pintype "bidirectional"))
    )
    (net (code "77") (name "unconnected-(U$3-PA4{slash}SPI1_NSS-Pad20)") (class "Default")
      (node (ref "U$3") (pin "20") (pinfunction "PA4/SPI1_NSS_20") (pintype "bidirectional"))
    )
    (net (code "78") (name "unconnected-(U$3-PA5{slash}SPI1_SCK-Pad21)") (class "Default")
      (node (ref "U$3") (pin "21") (pinfunction "PA5/SPI1_SCK_21") (pintype "bidirectional"))
    )
    (net (code "79") (name "unconnected-(U$3-PA12-Pad45)") (class "Default")
      (node (ref "U$3") (pin "45") (pinfunction "PA12_45") (pintype "bidirectional"))
    )
    (net (code "80") (name "unconnected-(U$3-PB0-Pad26)") (class "Default")
      (node (ref "U$3") (pin "26") (pinfunction "PB0_26") (pintype "bidirectional"))
    )
    (net (code "81") (name "unconnected-(U$3-PB1-Pad27)") (class "Default")
      (node (ref "U$3") (pin "27") (pinfunction "PB1_27") (pintype "bidirectional"))
    )
    (net (code "82") (name "unconnected-(U$3-PB2-BOOT1-Pad28)") (class "Default")
      (node (ref "U$3") (pin "28") (pinfunction "PB2-BOOT1_28") (pintype "bidirectional"))
    )
    (net (code "83") (name "unconnected-(U$3-PB4{slash}JTRST-Pad56)") (class "Default")
      (node (ref "U$3") (pin "56") (pinfunction "PB4/JTRST_56") (pintype "bidirectional"))
    )
    (net (code "84") (name "unconnected-(U$3-PB5-Pad57)") (class "Default")
      (node (ref "U$3") (pin "57") (pinfunction "PB5_57") (pintype "bidirectional"))
    )
    (net (code "85") (name "unconnected-(U$3-PB6-Pad58)") (class "Default")
      (node (ref "U$3") (pin "58") (pinfunction "PB6_58") (pintype "bidirectional"))
    )
    (net (code "86") (name "unconnected-(U$3-PB7-Pad59)") (class "Default")
      (node (ref "U$3") (pin "59") (pinfunction "PB7_59") (pintype "bidirectional"))
    )
    (net (code "87") (name "unconnected-(U$3-PB10-Pad29)") (class "Default")
      (node (ref "U$3") (pin "29") (pinfunction "PB10_29") (pintype "bidirectional"))
    )
    (net (code "88") (name "unconnected-(U$3-PB12{slash}I2S2_WS-Pad33)") (class "Default")
      (node (ref "U$3") (pin "33") (pinfunction "PB12/I2S2_WS_33") (pintype "bidirectional"))
    )
    (net (code "89") (name "unconnected-(U$3-PB13{slash}I2S2_CK-Pad34)") (class "Default")
      (node (ref "U$3") (pin "34") (pinfunction "PB13/I2S2_CK_34") (pintype "bidirectional"))
    )
    (net (code "90") (name "unconnected-(U$3-PB14{slash}I2S2_XD-Pad35)") (class "Default")
      (node (ref "U$3") (pin "35") (pinfunction "PB14/I2S2_XD_35") (pintype "bidirectional"))
    )
    (net (code "91") (name "unconnected-(U$3-PB15{slash}I2S2_SD-Pad36)") (class "Default")
      (node (ref "U$3") (pin "36") (pinfunction "PB15/I2S2_SD_36") (pintype "bidirectional"))
    )
    (net (code "92") (name "unconnected-(U$3-PC2-Pad10)") (class "Default")
      (node (ref "U$3") (pin "10") (pinfunction "PC2_10") (pintype "bidirectional"))
    )
    (net (code "93") (name "unconnected-(U$3-PC3-Pad11)") (class "Default")
      (node (ref "U$3") (pin "11") (pinfunction "PC3_11") (pintype "bidirectional"))
    )
    (net (code "94") (name "unconnected-(U$3-PC5-Pad25)") (class "Default")
      (node (ref "U$3") (pin "25") (pinfunction "PC5_25") (pintype "bidirectional"))
    )
    (net (code "95") (name "unconnected-(U$3-PC6{slash}I2S2_MCK-Pad37)") (class "Default")
      (node (ref "U$3") (pin "37") (pinfunction "PC6/I2S2_MCK_37") (pintype "bidirectional"))
    )
    (net (code "96") (name "unconnected-(U$3-PC7-Pad38)") (class "Default")
      (node (ref "U$3") (pin "38") (pinfunction "PC7_38") (pintype "bidirectional"))
    )
    (net (code "97") (name "unconnected-(U$3-PC8{slash}SDIO_D0-Pad39)") (class "Default")
      (node (ref "U$3") (pin "39") (pinfunction "PC8/SDIO_D0_39") (pintype "bidirectional"))
    )
    (net (code "98") (name "unconnected-(U$3-PC9{slash}SDIO_D1-Pad40)") (class "Default")
      (node (ref "U$3") (pin "40") (pinfunction "PC9/SDIO_D1_40") (pintype "bidirectional"))
    )
    (net (code "99") (name "unconnected-(U$3-PC13-Pad2)") (class "Default")
      (node (ref "U$3") (pin "2") (pinfunction "PC13_2") (pintype "bidirectional"))
    )
    (net (code "100") (name "unconnected-(U$3-PC14-Pad3)") (class "Default")
      (node (ref "U$3") (pin "3") (pinfunction "PC14_3") (pintype "bidirectional"))
    )
    (net (code "101") (name "unconnected-(U$3-PC15-Pad4)") (class "Default")
      (node (ref "U$3") (pin "4") (pinfunction "PC15_4") (pintype "bidirectional"))
    )
    (net (code "102") (name "unconnected-(U$3-PD2{slash}SDIO_CMD-Pad54)") (class "Default")
      (node (ref "U$3") (pin "54") (pinfunction "PD2/SDIO_CMD_54") (pintype "bidirectional"))
    )
    (net (code "103") (name "unconnected-(U$3-PH1-Pad6)") (class "Default")
      (node (ref "U$3") (pin "6") (pinfunction "PH1_6") (pintype "bidirectional"))
    )
  )
)
